# water_heater_02.net
KiCad netlist of a schematic drawn in Altium Designer
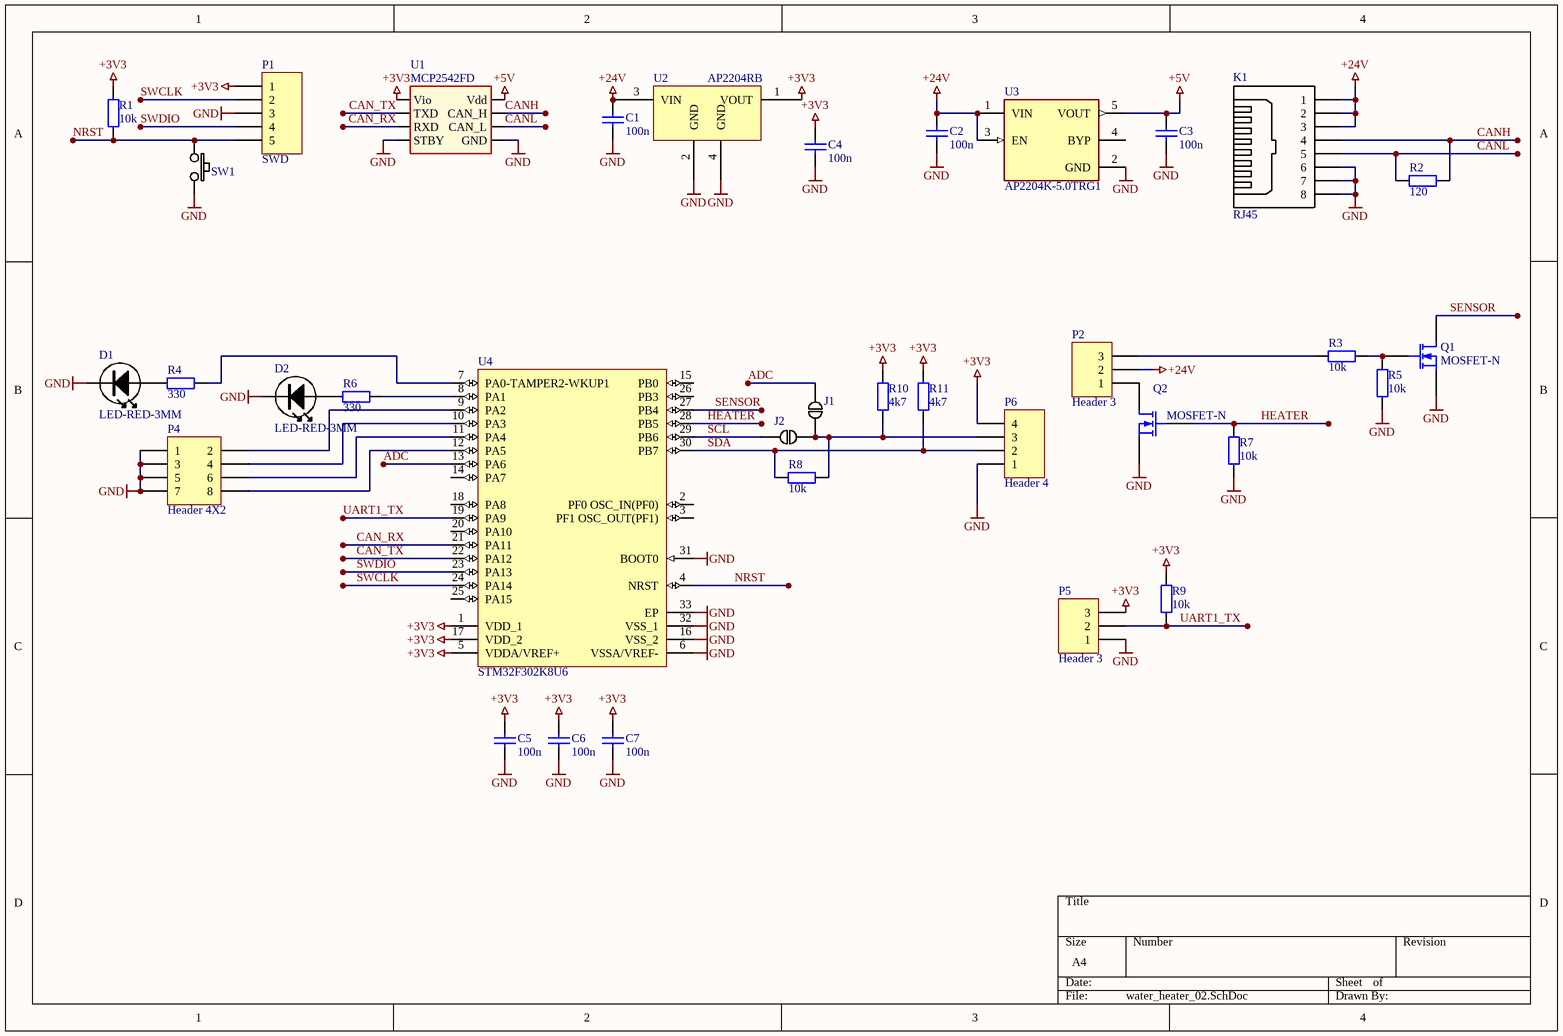
[diagram p0: water_heater_02.SchDoc]

(export (version "E")
  (design (tool "Eeschema 10.0.6"))
  (components
    (comp (ref "C1")
      (value "100n")
      (footprint "0603C-GENERIC")
      (description "Capacitor")
      (fields (field (name "Comment") "Cap") (field (name "PUBLISHER") "Altium Limited"))
      (libsource (lib "Miscellaneous Devices") (part "Cap"))
    )
    (comp (ref "C2")
      (value "100n")
      (footprint "0603C-GENERIC")
      (description "Capacitor")
      (fields (field (name "Comment") "Cap") (field (name "PUBLISHER") "Altium Limited"))
      (libsource (lib "Miscellaneous Devices") (part "Cap"))
    )
    (comp (ref "C3")
      (value "100n")
      (footprint "0603C-GENERIC")
      (description "Capacitor")
      (fields (field (name "Comment") "Cap") (field (name "PUBLISHER") "Altium Limited"))
      (libsource (lib "Miscellaneous Devices") (part "Cap"))
    )
    (comp (ref "C4")
      (value "100n")
      (footprint "0603C-GENERIC")
      (description "Capacitor")
      (fields (field (name "Comment") "Cap") (field (name "PUBLISHER") "Altium Limited"))
      (libsource (lib "Miscellaneous Devices") (part "Cap"))
    )
    (comp (ref "C5")
      (value "100n")
      (footprint "0603C-GENERIC")
      (description "Capacitor")
      (fields (field (name "Comment") "Cap") (field (name "PUBLISHER") "Altium Limited"))
      (libsource (lib "Miscellaneous Devices") (part "Cap"))
    )
    (comp (ref "C6")
      (value "100n")
      (footprint "0603C-GENERIC")
      (description "Capacitor")
      (fields (field (name "Comment") "Cap") (field (name "PUBLISHER") "Altium Limited"))
      (libsource (lib "Miscellaneous Devices") (part "Cap"))
    )
    (comp (ref "C7")
      (value "100n")
      (footprint "0603C-GENERIC")
      (description "Capacitor")
      (fields (field (name "Comment") "Cap") (field (name "PUBLISHER") "Altium Limited"))
      (libsource (lib "Miscellaneous Devices") (part "Cap"))
    )
    (comp (ref "D1")
      (value "LED-RED-3MM")
      (footprint "LED-3MM-GREEN")
      (description "LED-GREEN-3MM")
      (libsource (lib "vh_altium_library") (part "LED-GREEN-3MM"))
    )
    (comp (ref "D2")
      (value "LED-RED-3MM")
      (footprint "LED-3MM-GREEN")
      (description "LED-GREEN-3MM")
      (libsource (lib "vh_altium_library") (part "LED-GREEN-3MM"))
    )
    (comp (ref "J1")
      (value "~")
      (footprint "BYPASS-MINI")
      (description "SOLDERDOT BYPASS")
      (libsource (lib "vh_altium_library") (part "BYPASS-MINI"))
    )
    (comp (ref "J2")
      (value "~")
      (footprint "BYPASS-MINI")
      (description "SOLDERDOT BYPASS")
      (libsource (lib "vh_altium_library") (part "BYPASS-MINI"))
    )
    (comp (ref "K1") (value "RJ45") (footprint "rj45") (libsource (lib "vh_altium_library") (part "RJ45")))
    (comp (ref "P1")
      (value "SWD")
      (footprint "HDR1X5")
      (description "Header, 5-Pin")
      (fields (field (name "PUBLISHER") "Altium Limited"))
      (libsource (lib "Miscellaneous Connectors") (part "Header 5"))
    )
    (comp (ref "P2")
      (value "Header 3")
      (footprint "XY301V-3P (5.00)")
      (description "Header, 3-Pin")
      (fields (field (name "PUBLISHER") "Altium Limited"))
      (libsource (lib "Miscellaneous Connectors") (part "Header 3"))
    )
    (comp (ref "P4")
      (value "Header 4X2")
      (footprint "HDR2X4")
      (description "Header, 4-Pin, Dual row")
      (fields (field (name "PUBLISHER") "Altium Limited"))
      (libsource (lib "Miscellaneous Connectors") (part "Header 4X2"))
    )
    (comp (ref "P5")
      (value "Header 3")
      (footprint "XY301V-3P (5.00)")
      (description "Header, 3-Pin")
      (fields (field (name "PUBLISHER") "Altium Limited"))
      (libsource (lib "Miscellaneous Connectors") (part "Header 3"))
    )
    (comp (ref "P6")
      (value "Header 4")
      (footprint "B4B-XH-A")
      (description "Header, 4-Pin")
      (fields (field (name "PUBLISHER") "Altium Limited"))
      (libsource (lib "Miscellaneous Connectors") (part "Header 4"))
    )
    (comp (ref "Q1")
      (value "MOSFET-N")
      (footprint "SOT23-123")
      (description "N-Channel MOSFET")
      (fields (field (name "PUBLISHER") "Altium Limited"))
      (libsource (lib "Miscellaneous Devices") (part "MOSFET-N"))
    )
    (comp (ref "Q2")
      (value "MOSFET-N")
      (footprint "SOT23-123")
      (description "N-Channel MOSFET")
      (fields (field (name "PUBLISHER") "Altium Limited"))
      (libsource (lib "Miscellaneous Devices") (part "MOSFET-N"))
    )
    (comp (ref "R1")
      (value "10k")
      (footprint "0603R-GENERIC")
      (description "Resistor")
      (fields (field (name "Comment") "Res2") (field (name "PUBLISHER") "Altium Limited"))
      (libsource (lib "Miscellaneous Devices") (part "Res2"))
    )
    (comp (ref "R2")
      (value "120")
      (footprint "0603R-GENERIC")
      (description "Resistor")
      (fields (field (name "Comment") "Res2") (field (name "PUBLISHER") "Altium Limited"))
      (libsource (lib "") (part "Res2_1"))
    )
    (comp (ref "R3")
      (value "10k")
      (footprint "0603R-GENERIC")
      (description "Resistor")
      (fields (field (name "Comment") "Res2") (field (name "PUBLISHER") "Altium Limited"))
      (libsource (lib "") (part "Res2_1"))
    )
    (comp (ref "R4")
      (value "330")
      (footprint "0603R-GENERIC")
      (description "Resistor")
      (fields (field (name "Comment") "Res2") (field (name "PUBLISHER") "Altium Limited"))
      (libsource (lib "") (part "Res2_1"))
    )
    (comp (ref "R5")
      (value "10k")
      (footprint "0603R-GENERIC")
      (description "Resistor")
      (fields (field (name "Comment") "Res2") (field (name "PUBLISHER") "Altium Limited"))
      (libsource (lib "") (part "Res2_2"))
    )
    (comp (ref "R6")
      (value "330")
      (footprint "0603R-GENERIC")
      (description "Resistor")
      (fields (field (name "Comment") "Res2") (field (name "PUBLISHER") "Altium Limited"))
      (libsource (lib "") (part "Res2_1"))
    )
    (comp (ref "R7")
      (value "10k")
      (footprint "0603R-GENERIC")
      (description "Resistor")
      (fields (field (name "Comment") "Res2") (field (name "PUBLISHER") "Altium Limited"))
      (libsource (lib "") (part "Res2_2"))
    )
    (comp (ref "R8")
      (value "10k")
      (footprint "0603R-GENERIC")
      (description "Resistor")
      (fields (field (name "Comment") "Res2") (field (name "PUBLISHER") "Altium Limited"))
      (libsource (lib "") (part "Res2_1"))
    )
    (comp (ref "R9")
      (value "10k")
      (footprint "0603R-GENERIC")
      (description "Resistor")
      (fields (field (name "Comment") "Res2") (field (name "PUBLISHER") "Altium Limited"))
      (libsource (lib "") (part "Res2_2"))
    )
    (comp (ref "R10")
      (value "4k7")
      (footprint "0603R-GENERIC")
      (description "Resistor")
      (fields (field (name "Comment") "Res2") (field (name "PUBLISHER") "Altium Limited"))
      (libsource (lib "Miscellaneous Devices") (part "Res2"))
    )
    (comp (ref "R11")
      (value "4k7")
      (footprint "0603R-GENERIC")
      (description "Resistor")
      (fields (field (name "Comment") "Res2") (field (name "PUBLISHER") "Altium Limited"))
      (libsource (lib "Miscellaneous Devices") (part "Res2"))
    )
    (comp (ref "SW1")
      (value "SW-PB-BLACK-SMD")
      (footprint "PTS810")
      (description "PUSHBUTTON SWITCH 6MM SMD")
      (libsource (lib "vh_altium_library") (part "SW-PB-BLACK-SMD"))
    )
    (comp (ref "U1") (value "MCP2542FD") (footprint "SO8") (libsource (lib "suciastky2") (part "MCP2542FD")))
    (comp (ref "U2") (value "AP2204RB") (footprint "SOT-89") (libsource (lib "lib") (part "AP2204RB")))
    (comp (ref "U3")
      (value "AP2204K-5.0TRG1")
      (footprint "FP-SOT25-IPC_B")
      (description "IC REG LINEAR 3.3V 150MA SOT23-5")
      (fields
        (field (name "MANUFACTURER PART NUMBER") "AP2202K-3.3TRG1")
        (field (name "OCTOPART") "https://octopart.com/ap2202k-3.3trg1-diodes+inc.-30954618")
      )
      (libsource (lib "Altium Content Vault") (part "CMP-12756-000010-1"))
    )
    (comp (ref "U4")
      (value "STM32F302K8U6")
      (footprint "UFQFPN32_M")
      (fields (field (name "MANUFACTURER") "STMicroelectronics"))
      (libsource (lib "Altium Content Vault") (part "STM-STM32F302X6_X8-UFQFPN-32"))
    )
  )
  (nets
    (net (code "1") (name "+3V3") (class "Default")
      (node (ref "C4") (pin "2") (pinfunction "2_2") (pintype "passive"))
      (node (ref "C5") (pin "1") (pinfunction "1_1") (pintype "passive"))
      (node (ref "C6") (pin "1") (pinfunction "1_1") (pintype "passive"))
      (node (ref "C7") (pin "1") (pinfunction "1_1") (pintype "passive"))
      (node (ref "P1") (pin "1") (pinfunction "1_1") (pintype "passive"))
      (node (ref "P5") (pin "3") (pinfunction "3_3") (pintype "passive"))
      (node (ref "P6") (pin "4") (pinfunction "4_4") (pintype "passive"))
      (node (ref "R1") (pin "2") (pinfunction "2_2") (pintype "passive"))
      (node (ref "R10") (pin "2") (pinfunction "2_2") (pintype "passive"))
      (node (ref "R11") (pin "2") (pinfunction "2_2") (pintype "passive"))
      (node (ref "R9") (pin "1") (pinfunction "1_1") (pintype "passive"))
      (node (ref "U1") (pin "5") (pinfunction "Vio_5") (pintype "passive"))
      (node (ref "U2") (pin "1") (pinfunction "VOUT_1") (pintype "passive"))
      (node (ref "U4") (pin "1") (pinfunction "VDD_1_1") (pintype "power_in"))
      (node (ref "U4") (pin "17") (pinfunction "VDD_2_17") (pintype "power_in"))
      (node (ref "U4") (pin "5") (pinfunction "VDDA/VREF+_5") (pintype "power_in"))
    )
    (net (code "2") (name "+5V") (class "Default")
      (node (ref "C3") (pin "2") (pinfunction "2_2") (pintype "passive"))
      (node (ref "U1") (pin "3") (pinfunction "Vdd_3") (pintype "passive"))
      (node (ref "U3") (pin "5") (pinfunction "VOUT_5") (pintype "output"))
    )
    (net (code "3") (name "+24V") (class "Default")
      (node (ref "C1") (pin "2") (pinfunction "2_2") (pintype "passive"))
      (node (ref "C2") (pin "2") (pinfunction "2_2") (pintype "passive"))
      (node (ref "K1") (pin "1") (pinfunction "1_1") (pintype "passive"))
      (node (ref "K1") (pin "2") (pinfunction "2_2") (pintype "passive"))
      (node (ref "K1") (pin "3") (pinfunction "3_3") (pintype "passive"))
      (node (ref "P2") (pin "2") (pinfunction "2_2") (pintype "passive"))
      (node (ref "U2") (pin "3") (pinfunction "VIN_3") (pintype "passive"))
      (node (ref "U3") (pin "1") (pinfunction "VIN_1") (pintype "power_in"))
      (node (ref "U3") (pin "3") (pinfunction "EN_3") (pintype "input"))
    )
    (net (code "4") (name "/ADC") (class "Default")
      (node (ref "J1") (pin "1") (pinfunction "1_1") (pintype "passive"))
      (node (ref "U4") (pin "13") (pinfunction "PA6_13") (pintype "bidirectional"))
    )
    (net (code "5") (name "/CANH") (class "Default")
      (node (ref "K1") (pin "4") (pinfunction "4_4") (pintype "passive"))
      (node (ref "R2") (pin "2") (pinfunction "2_2") (pintype "passive"))
      (node (ref "U1") (pin "7") (pinfunction "CAN_H_7") (pintype "passive"))
    )
    (net (code "6") (name "/CANL") (class "Default")
      (node (ref "K1") (pin "5") (pinfunction "5_5") (pintype "passive"))
      (node (ref "R2") (pin "1") (pinfunction "1_1") (pintype "passive"))
      (node (ref "U1") (pin "6") (pinfunction "CAN_L_6") (pintype "passive"))
    )
    (net (code "7") (name "/CAN_RX") (class "Default")
      (node (ref "U1") (pin "4") (pinfunction "RXD_4") (pintype "passive"))
      (node (ref "U4") (pin "21") (pinfunction "PA11_21") (pintype "bidirectional"))
    )
    (net (code "8") (name "/CAN_TX") (class "Default")
      (node (ref "U1") (pin "1") (pinfunction "TXD_1") (pintype "passive"))
      (node (ref "U4") (pin "22") (pinfunction "PA12_22") (pintype "bidirectional"))
    )
    (net (code "9") (name "/HEATER") (class "Default")
      (node (ref "Q2") (pin "2") (pinfunction "G_2") (pintype "passive"))
      (node (ref "R7") (pin "1") (pinfunction "1_1") (pintype "passive"))
      (node (ref "U4") (pin "28") (pinfunction "PB5_28") (pintype "bidirectional"))
    )
    (net (code "10") (name "/NRST") (class "Default")
      (node (ref "P1") (pin "5") (pinfunction "5_5") (pintype "passive"))
      (node (ref "R1") (pin "1") (pinfunction "1_1") (pintype "passive"))
      (node (ref "SW1") (pin "1") (pintype "passive"))
      (node (ref "U4") (pin "4") (pinfunction "NRST_4") (pintype "bidirectional"))
    )
    (net (code "11") (name "/SCL") (class "Default")
      (node (ref "J2") (pin "2") (pinfunction "2_2") (pintype "passive"))
      (node (ref "U4") (pin "29") (pinfunction "PB6_29") (pintype "bidirectional"))
    )
    (net (code "12") (name "/SDA") (class "Default")
      (node (ref "P6") (pin "2") (pinfunction "2_2") (pintype "passive"))
      (node (ref "R11") (pin "1") (pinfunction "1_1") (pintype "passive"))
      (node (ref "R8") (pin "1") (pinfunction "1_1") (pintype "passive"))
      (node (ref "U4") (pin "30") (pinfunction "PB7_30") (pintype "bidirectional"))
    )
    (net (code "13") (name "/SENSOR") (class "Default")
      (node (ref "Q1") (pin "1") (pinfunction "D_1") (pintype "passive"))
      (node (ref "U4") (pin "27") (pinfunction "PB4_27") (pintype "bidirectional"))
    )
    (net (code "14") (name "/SWCLK") (class "Default")
      (node (ref "P1") (pin "2") (pinfunction "2_2") (pintype "passive"))
      (node (ref "U4") (pin "24") (pinfunction "PA14_24") (pintype "bidirectional"))
    )
    (net (code "15") (name "/SWDIO") (class "Default")
      (node (ref "P1") (pin "4") (pinfunction "4_4") (pintype "passive"))
      (node (ref "U4") (pin "23") (pinfunction "PA13_23") (pintype "bidirectional"))
    )
    (net (code "16") (name "/UART1_TX") (class "Default")
      (node (ref "P5") (pin "2") (pinfunction "2_2") (pintype "passive"))
      (node (ref "R9") (pin "2") (pinfunction "2_2") (pintype "passive"))
      (node (ref "U4") (pin "19") (pinfunction "PA9_19") (pintype "bidirectional"))
    )
    (net (code "17") (name "GND") (class "Default")
      (node (ref "C1") (pin "1") (pinfunction "1_1") (pintype "passive"))
      (node (ref "C2") (pin "1") (pinfunction "1_1") (pintype "passive"))
      (node (ref "C3") (pin "1") (pinfunction "1_1") (pintype "passive"))
      (node (ref "C4") (pin "1") (pinfunction "1_1") (pintype "passive"))
      (node (ref "C5") (pin "2") (pinfunction "2_2") (pintype "passive"))
      (node (ref "C6") (pin "2") (pinfunction "2_2") (pintype "passive"))
      (node (ref "C7") (pin "2") (pinfunction "2_2") (pintype "passive"))
      (node (ref "D1") (pin "K") (pintype "passive"))
      (node (ref "D2") (pin "K") (pintype "passive"))
      (node (ref "K1") (pin "6") (pinfunction "6_6") (pintype "passive"))
      (node (ref "K1") (pin "7") (pinfunction "7_7") (pintype "passive"))
      (node (ref "K1") (pin "8") (pinfunction "8_8") (pintype "passive"))
      (node (ref "P1") (pin "3") (pinfunction "3_3") (pintype "passive"))
      (node (ref "P4") (pin "1") (pinfunction "1_1") (pintype "passive"))
      (node (ref "P4") (pin "3") (pinfunction "3_3") (pintype "passive"))
      (node (ref "P4") (pin "5") (pinfunction "5_5") (pintype "passive"))
      (node (ref "P4") (pin "7") (pinfunction "7_7") (pintype "passive"))
      (node (ref "P5") (pin "1") (pinfunction "1_1") (pintype "passive"))
      (node (ref "P6") (pin "1") (pinfunction "1_1") (pintype "passive"))
      (node (ref "Q1") (pin "3") (pinfunction "S_3") (pintype "passive"))
      (node (ref "Q2") (pin "3") (pinfunction "S_3") (pintype "passive"))
      (node (ref "R5") (pin "2") (pinfunction "2_2") (pintype "passive"))
      (node (ref "R7") (pin "2") (pinfunction "2_2") (pintype "passive"))
      (node (ref "SW1") (pin "2") (pintype "passive"))
      (node (ref "U1") (pin "2") (pinfunction "GND_2") (pintype "passive"))
      (node (ref "U1") (pin "8") (pinfunction "STBY_8") (pintype "passive"))
      (node (ref "U2") (pin "2") (pinfunction "GND_2") (pintype "passive"))
      (node (ref "U2") (pin "4") (pinfunction "GND_4") (pintype "passive"))
      (node (ref "U3") (pin "2") (pinfunction "GND_2") (pintype "power_in"))
      (node (ref "U4") (pin "16") (pinfunction "VSS_2_16") (pintype "power_in"))
      (node (ref "U4") (pin "31") (pinfunction "BOOT0_31") (pintype "input"))
      (node (ref "U4") (pin "32") (pinfunction "VSS_1_32") (pintype "power_in"))
      (node (ref "U4") (pin "33") (pinfunction "EP_33") (pintype "passive"))
      (node (ref "U4") (pin "6") (pinfunction "VSSA/VREF-_6") (pintype "power_in"))
    )
    (net (code "18") (name "Net-(D1-PadA)") (class "Default")
      (node (ref "D1") (pin "A") (pintype "passive"))
      (node (ref "R4") (pin "1") (pinfunction "1_1") (pintype "passive"))
    )
    (net (code "19") (name "Net-(D2-PadA)") (class "Default")
      (node (ref "D2") (pin "A") (pintype "passive"))
      (node (ref "R6") (pin "1") (pinfunction "1_1") (pintype "passive"))
    )
    (net (code "20") (name "Net-(J1-Pad2)") (class "Default")
      (node (ref "J1") (pin "2") (pinfunction "2_2") (pintype "passive"))
      (node (ref "J2") (pin "1") (pinfunction "1_1") (pintype "passive"))
      (node (ref "P6") (pin "3") (pinfunction "3_3") (pintype "passive"))
      (node (ref "R10") (pin "1") (pinfunction "1_1") (pintype "passive"))
      (node (ref "R8") (pin "2") (pinfunction "2_2") (pintype "passive"))
    )
    (net (code "21") (name "Net-(P2-Pad3)") (class "Default")
      (node (ref "P2") (pin "3") (pinfunction "3_3") (pintype "passive"))
      (node (ref "R3") (pin "1") (pinfunction "1_1") (pintype "passive"))
    )
    (net (code "22") (name "Net-(Q1-G)") (class "Default")
      (node (ref "Q1") (pin "2") (pinfunction "G_2") (pintype "passive"))
      (node (ref "R3") (pin "2") (pinfunction "2_2") (pintype "passive"))
      (node (ref "R5") (pin "1") (pinfunction "1_1") (pintype "passive"))
    )
    (net (code "23") (name "Net-(Q2-D)") (class "Default")
      (node (ref "P2") (pin "1") (pinfunction "1_1") (pintype "passive"))
      (node (ref "Q2") (pin "1") (pinfunction "D_1") (pintype "passive"))
    )
    (net (code "24") (name "Net-(U4-PA0-TAMPER2-WKUP1)") (class "Default")
      (node (ref "R4") (pin "2") (pinfunction "2_2") (pintype "passive"))
      (node (ref "U4") (pin "7") (pinfunction "PA0-TAMPER2-WKUP1_7") (pintype "bidirectional"))
    )
    (net (code "25") (name "Net-(U4-PA1)") (class "Default")
      (node (ref "R6") (pin "2") (pinfunction "2_2") (pintype "passive"))
      (node (ref "U4") (pin "8") (pinfunction "PA1_8") (pintype "bidirectional"))
    )
    (net (code "26") (name "Net-(U4-PA2)") (class "Default")
      (node (ref "P4") (pin "2") (pinfunction "2_2") (pintype "passive"))
      (node (ref "U4") (pin "9") (pinfunction "PA2_9") (pintype "bidirectional"))
    )
    (net (code "27") (name "Net-(U4-PA3)") (class "Default")
      (node (ref "P4") (pin "4") (pinfunction "4_4") (pintype "passive"))
      (node (ref "U4") (pin "10") (pinfunction "PA3_10") (pintype "bidirectional"))
    )
    (net (code "28") (name "Net-(U4-PA4)") (class "Default")
      (node (ref "P4") (pin "6") (pinfunction "6_6") (pintype "passive"))
      (node (ref "U4") (pin "11") (pinfunction "PA4_11") (pintype "bidirectional"))
    )
    (net (code "29") (name "Net-(U4-PA5)") (class "Default")
      (node (ref "P4") (pin "8") (pinfunction "8_8") (pintype "passive"))
      (node (ref "U4") (pin "12") (pinfunction "PA5_12") (pintype "bidirectional"))
    )
    (net (code "30") (name "unconnected-(U3-BYP-Pad4)") (class "Default")
      (node (ref "U3") (pin "4") (pinfunction "BYP_4") (pintype "passive"))
    )
    (net (code "31") (name "unconnected-(U4-PA7-Pad14)") (class "Default")
      (node (ref "U4") (pin "14") (pinfunction "PA7_14") (pintype "bidirectional"))
    )
    (net (code "32") (name "unconnected-(U4-PA8-Pad18)") (class "Default")
      (node (ref "U4") (pin "18") (pinfunction "PA8_18") (pintype "bidirectional"))
    )
    (net (code "33") (name "unconnected-(U4-PA10-Pad20)") (class "Default")
      (node (ref "U4") (pin "20") (pinfunction "PA10_20") (pintype "bidirectional"))
    )
    (net (code "34") (name "unconnected-(U4-PA15-Pad25)") (class "Default")
      (node (ref "U4") (pin "25") (pinfunction "PA15_25") (pintype "bidirectional"))
    )
    (net (code "35") (name "unconnected-(U4-PB0-Pad15)") (class "Default")
      (node (ref "U4") (pin "15") (pinfunction "PB0_15") (pintype "bidirectional"))
    )
    (net (code "36") (name "unconnected-(U4-PB3-Pad26)") (class "Default")
      (node (ref "U4") (pin "26") (pinfunction "PB3_26") (pintype "bidirectional"))
    )
    (net (code "37") (name "unconnected-(U4-PF0_OSC_IN(PF0)-Pad2)") (class "Default")
      (node (ref "U4") (pin "2") (pinfunction "PF0_OSC_IN(PF0)_2") (pintype "bidirectional"))
    )
    (net (code "38") (name "unconnected-(U4-PF1_OSC_OUT(PF1)-Pad3)") (class "Default")
      (node (ref "U4") (pin "3") (pinfunction "PF1_OSC_OUT(PF1)_3") (pintype "bidirectional"))
    )
  )
)
